# 1-6.net
KiCad netlist of a schematic drawn in Altium Designer
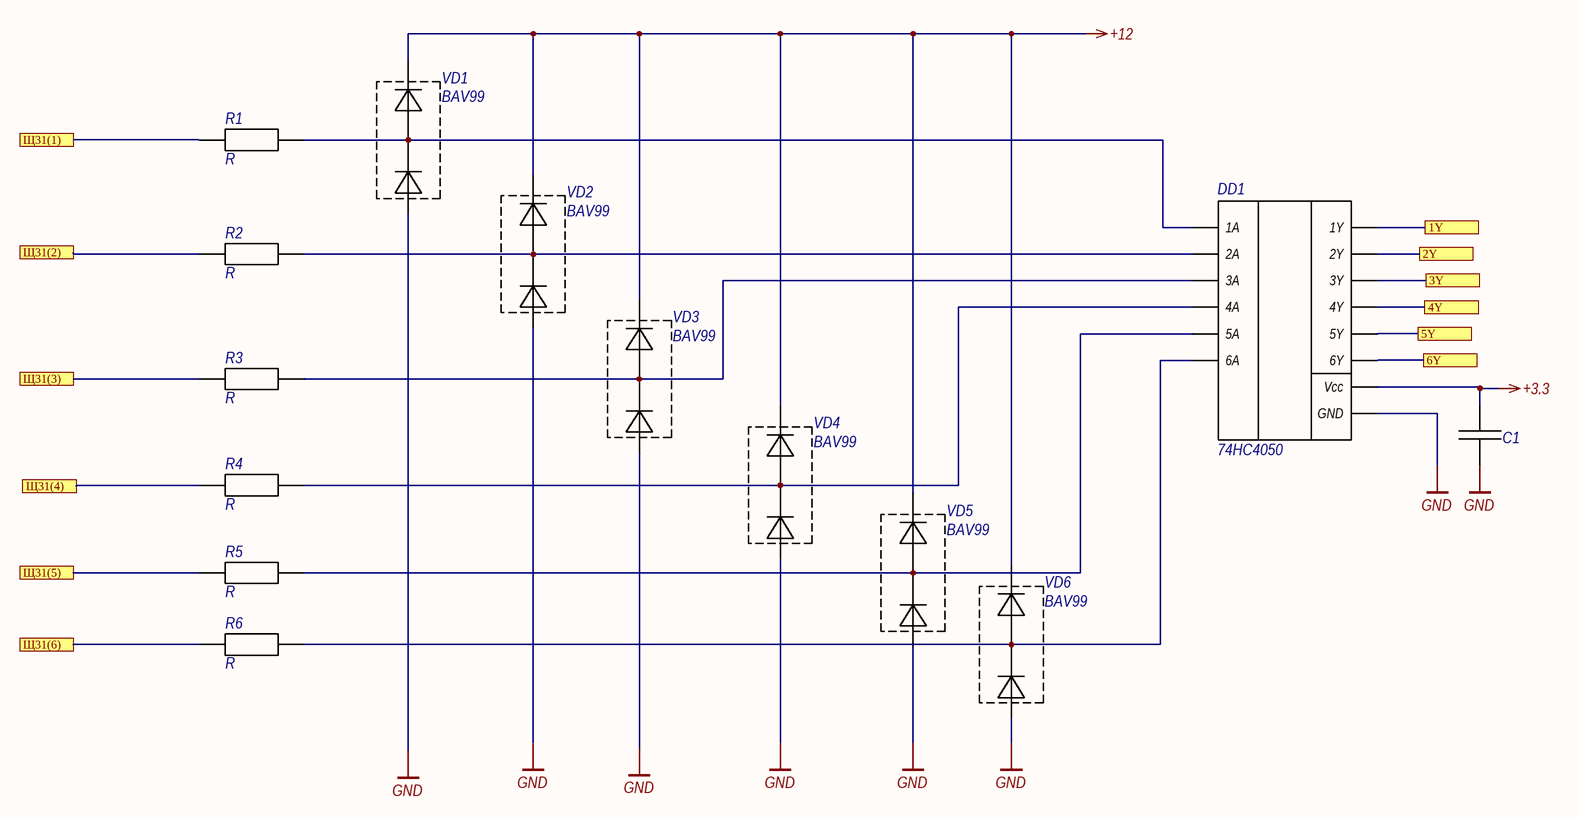
[diagram p0: ВХ Б (1-6).SchDoc]

(export (version "E")
  (design (tool "Eeschema 10.0.6"))
  (components
    (comp (ref "C1")
      (value "C(ceramic)")
      (footprint "C(ceramic)")
      (libsource (lib "UGO") (part "C(ceramic)"))
    )
    (comp (ref "DD1") (value "74HC4050") (footprint "74HC4050(51)") (libsource (lib "UGO") (part "74HC4050")))
    (comp (ref "R1") (value "R") (footprint "R") (libsource (lib "UGO") (part "R")))
    (comp (ref "R2") (value "R") (footprint "R") (libsource (lib "UGO") (part "R")))
    (comp (ref "R3") (value "R") (footprint "R") (libsource (lib "UGO") (part "R")))
    (comp (ref "R4") (value "R") (footprint "R") (libsource (lib "UGO") (part "R")))
    (comp (ref "R5") (value "R") (footprint "R") (libsource (lib "UGO") (part "R")))
    (comp (ref "R6") (value "R") (footprint "R") (libsource (lib "UGO") (part "R")))
    (comp (ref "VD1") (value "BAV99") (footprint "BAV99") (libsource (lib "UGO") (part "BAV99")))
    (comp (ref "VD2") (value "BAV99") (footprint "BAV99") (libsource (lib "UGO") (part "BAV99")))
    (comp (ref "VD3") (value "BAV99") (footprint "BAV99") (libsource (lib "UGO") (part "BAV99")))
    (comp (ref "VD4") (value "BAV99") (footprint "BAV99") (libsource (lib "UGO") (part "BAV99")))
    (comp (ref "VD5") (value "BAV99") (footprint "BAV99") (libsource (lib "UGO") (part "BAV99")))
    (comp (ref "VD6") (value "BAV99") (footprint "BAV99") (libsource (lib "UGO") (part "BAV99")))
  )
  (nets
    (net (code "1") (name "+3.3") (class "Default")
      (node (ref "C1") (pin "1") (pintype "passive"))
      (node (ref "DD1") (pin "1") (pinfunction "Vcc_1") (pintype "passive"))
    )
    (net (code "2") (name "+12") (class "Default")
      (node (ref "VD1") (pin "2") (pintype "passive"))
      (node (ref "VD2") (pin "2") (pintype "passive"))
      (node (ref "VD3") (pin "2") (pintype "passive"))
      (node (ref "VD4") (pin "2") (pintype "passive"))
      (node (ref "VD5") (pin "2") (pintype "passive"))
      (node (ref "VD6") (pin "2") (pintype "passive"))
    )
    (net (code "3") (name "/1Y") (class "Default")
      (node (ref "DD1") (pin "2") (pinfunction "1Y_2") (pintype "passive"))
    )
    (net (code "4") (name "/2Y") (class "Default")
      (node (ref "DD1") (pin "4") (pinfunction "2Y_4") (pintype "passive"))
    )
    (net (code "5") (name "/3Y") (class "Default")
      (node (ref "DD1") (pin "6") (pinfunction "3Y_6") (pintype "passive"))
    )
    (net (code "6") (name "/4Y") (class "Default")
      (node (ref "DD1") (pin "10") (pinfunction "4Y_10") (pintype "passive"))
    )
    (net (code "7") (name "/5Y") (class "Default")
      (node (ref "DD1") (pin "12") (pinfunction "5Y_12") (pintype "passive"))
    )
    (net (code "8") (name "/6Y") (class "Default")
      (node (ref "DD1") (pin "15") (pinfunction "6Y_15") (pintype "passive"))
    )
    (net (code "9") (name "/Щ31(1)") (class "Default") (node (ref "R1") (pin "1") (pintype "passive")))
    (net (code "10") (name "/Щ31(2)") (class "Default") (node (ref "R2") (pin "1") (pintype "passive")))
    (net (code "11") (name "/Щ31(3)") (class "Default") (node (ref "R3") (pin "1") (pintype "passive")))
    (net (code "12") (name "/Щ31(4)") (class "Default") (node (ref "R4") (pin "1") (pintype "passive")))
    (net (code "13") (name "/Щ31(5)") (class "Default") (node (ref "R5") (pin "1") (pintype "passive")))
    (net (code "14") (name "/Щ31(6)") (class "Default") (node (ref "R6") (pin "1") (pintype "passive")))
    (net (code "15") (name "GND") (class "Default")
      (node (ref "C1") (pin "2") (pintype "passive"))
      (node (ref "DD1") (pin "8") (pinfunction "GND_8") (pintype "passive"))
      (node (ref "VD1") (pin "1") (pintype "passive"))
      (node (ref "VD2") (pin "1") (pintype "passive"))
      (node (ref "VD3") (pin "1") (pintype "passive"))
      (node (ref "VD4") (pin "1") (pintype "passive"))
      (node (ref "VD5") (pin "1") (pintype "passive"))
      (node (ref "VD6") (pin "1") (pintype "passive"))
    )
    (net (code "16") (name "Net-(DD1-1A)") (class "Default")
      (node (ref "DD1") (pin "3") (pinfunction "1A_3") (pintype "passive"))
      (node (ref "R1") (pin "2") (pintype "passive"))
      (node (ref "VD1") (pin "3") (pintype "passive"))
    )
    (net (code "17") (name "Net-(DD1-2A)") (class "Default")
      (node (ref "DD1") (pin "5") (pinfunction "2A_5") (pintype "passive"))
      (node (ref "R2") (pin "2") (pintype "passive"))
      (node (ref "VD2") (pin "3") (pintype "passive"))
    )
    (net (code "18") (name "Net-(DD1-3A)") (class "Default")
      (node (ref "DD1") (pin "7") (pinfunction "3A_7") (pintype "passive"))
      (node (ref "R3") (pin "2") (pintype "passive"))
      (node (ref "VD3") (pin "3") (pintype "passive"))
    )
    (net (code "19") (name "Net-(DD1-4A)") (class "Default")
      (node (ref "DD1") (pin "9") (pinfunction "4A_9") (pintype "passive"))
      (node (ref "R4") (pin "2") (pintype "passive"))
      (node (ref "VD4") (pin "3") (pintype "passive"))
    )
    (net (code "20") (name "Net-(DD1-5A)") (class "Default")
      (node (ref "DD1") (pin "11") (pinfunction "5A_11") (pintype "passive"))
      (node (ref "R5") (pin "2") (pintype "passive"))
      (node (ref "VD5") (pin "3") (pintype "passive"))
    )
    (net (code "21") (name "Net-(DD1-6A)") (class "Default")
      (node (ref "DD1") (pin "14") (pinfunction "6A_14") (pintype "passive"))
      (node (ref "R6") (pin "2") (pintype "passive"))
      (node (ref "VD6") (pin "3") (pintype "passive"))
    )
  )
)
